# Metaldetector2.net
KiCad netlist of a schematic drawn in EAGLE
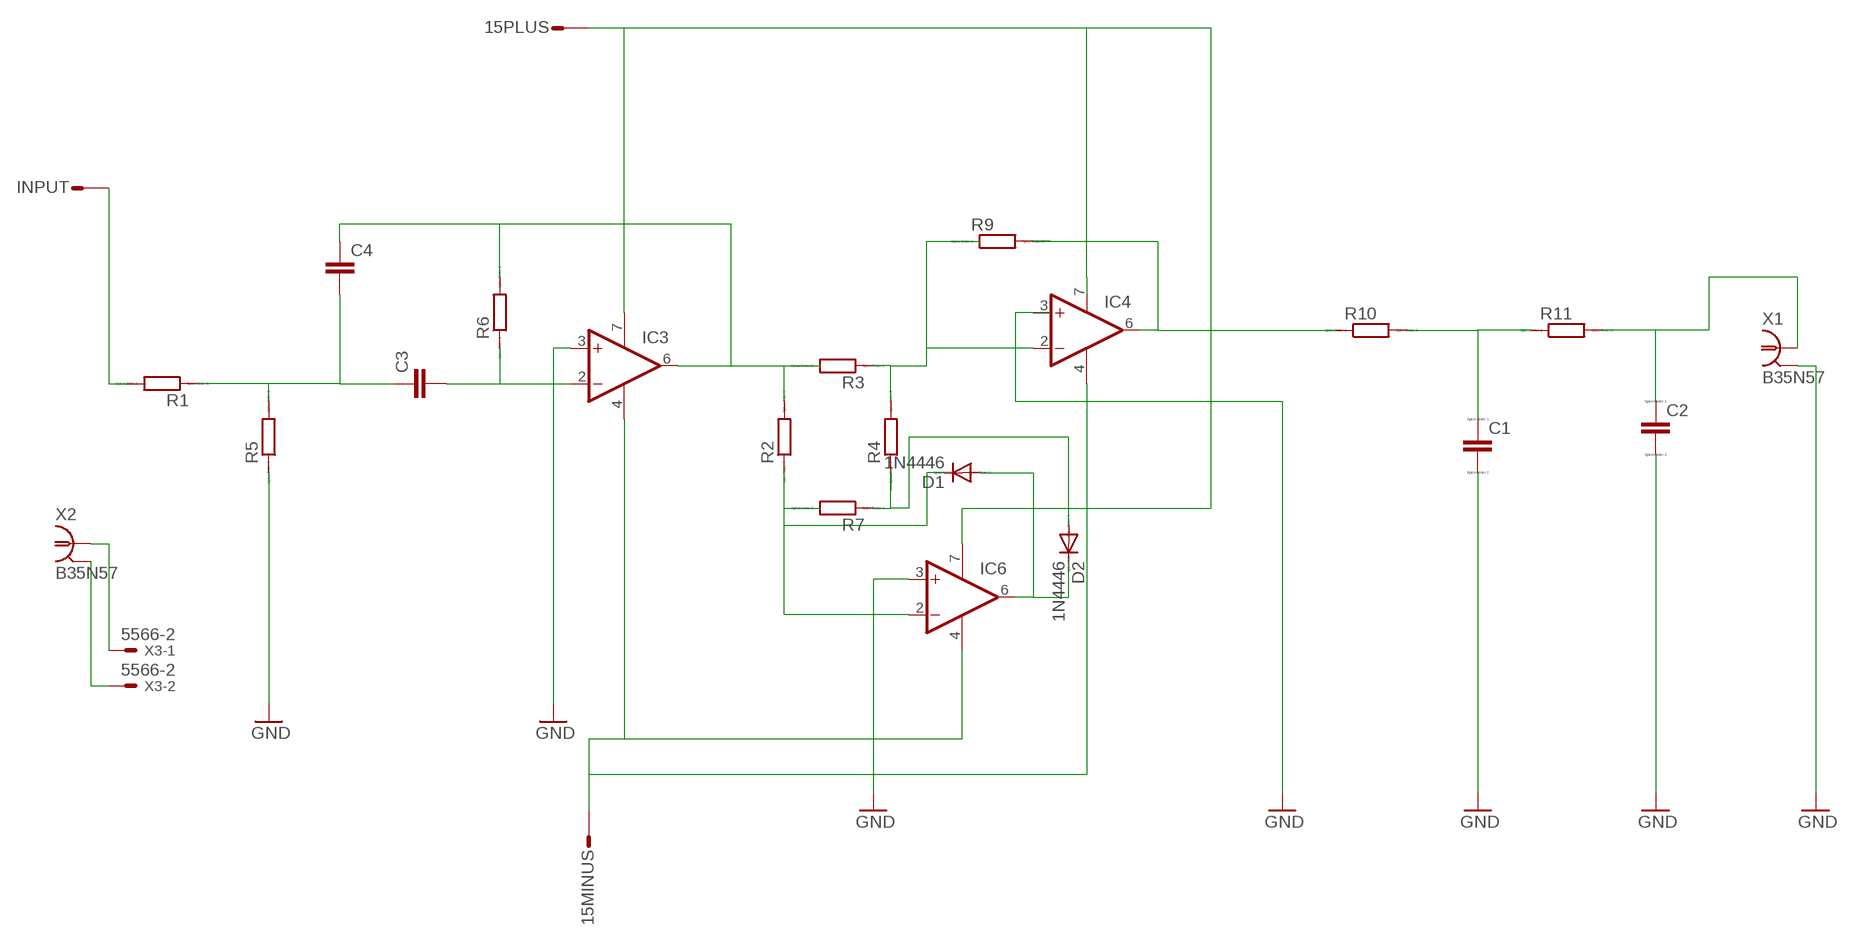
[diagram p0: schematic, sheet 1]

(export (version "E")
  (design (tool "Eeschema 10.0.6"))
  (components
    (comp (ref "15MINUS")
      (value "ST2,8")
      (footprint "eagle-import:ST2,8")
      (libsource (lib "eagle-import") (part "ST2,8"))
    )
    (comp (ref "15PLUS")
      (value "ST2,8")
      (footprint "eagle-import:ST2,8")
      (libsource (lib "eagle-import") (part "ST2,8"))
    )
    (comp (ref "C1")
      (value "C-EU025-040X050")
      (footprint "eagle-import:C025-040X050")
      (libsource (lib "eagle-import") (part "C-EU025-040X050"))
    )
    (comp (ref "C2")
      (value "C-EU025-040X050")
      (footprint "eagle-import:C025-040X050")
      (libsource (lib "eagle-import") (part "C-EU025-040X050"))
    )
    (comp (ref "C3")
      (value "C2.5/5")
      (footprint "eagle-import:C2.5-5")
      (libsource (lib "eagle-import") (part "C2.5/5"))
    )
    (comp (ref "C4")
      (value "C2.5/5")
      (footprint "eagle-import:C2.5-5")
      (libsource (lib "eagle-import") (part "C2.5/5"))
    )
    (comp (ref "D1")
      (value "1N4446")
      (footprint "eagle-import:DO35-10")
      (libsource (lib "eagle-import") (part "1N4446"))
    )
    (comp (ref "D2")
      (value "1N4446")
      (footprint "eagle-import:DO35-10")
      (libsource (lib "eagle-import") (part "1N4446"))
    )
    (comp (ref "IC3")
      (value "1AMP_P7+4N")
      (footprint "eagle-import:DIL08")
      (libsource (lib "eagle-import") (part "1AMP_P7+4N"))
    )
    (comp (ref "IC4")
      (value "1AMP_P7+4N")
      (footprint "eagle-import:DIL08")
      (libsource (lib "eagle-import") (part "1AMP_P7+4N"))
    )
    (comp (ref "IC6")
      (value "1AMP_P7+4N")
      (footprint "eagle-import:DIL08")
      (libsource (lib "eagle-import") (part "1AMP_P7+4N"))
    )
    (comp (ref "INPUT")
      (value "ST2,8")
      (footprint "eagle-import:ST2,8")
      (libsource (lib "eagle-import") (part "ST2,8"))
    )
    (comp (ref "R1")
      (value "R0207/10")
      (footprint "eagle-import:0207_10")
      (libsource (lib "eagle-import") (part "R0207/10"))
    )
    (comp (ref "R2")
      (value "R0207/10")
      (footprint "eagle-import:0207_10")
      (libsource (lib "eagle-import") (part "R0207/10"))
    )
    (comp (ref "R3")
      (value "R0207/10")
      (footprint "eagle-import:0207_10")
      (libsource (lib "eagle-import") (part "R0207/10"))
    )
    (comp (ref "R4")
      (value "R0207/10")
      (footprint "eagle-import:0207_10")
      (libsource (lib "eagle-import") (part "R0207/10"))
    )
    (comp (ref "R5")
      (value "R0207/10")
      (footprint "eagle-import:0207_10")
      (libsource (lib "eagle-import") (part "R0207/10"))
    )
    (comp (ref "R6")
      (value "R0207/10")
      (footprint "eagle-import:0207_10")
      (libsource (lib "eagle-import") (part "R0207/10"))
    )
    (comp (ref "R7")
      (value "R0207/10")
      (footprint "eagle-import:0207_10")
      (libsource (lib "eagle-import") (part "R0207/10"))
    )
    (comp (ref "R9")
      (value "R0207/10")
      (footprint "eagle-import:0207_10")
      (libsource (lib "eagle-import") (part "R0207/10"))
    )
    (comp (ref "R10")
      (value "R0204/7")
      (footprint "eagle-import:0204_7")
      (libsource (lib "eagle-import") (part "R0204/7"))
    )
    (comp (ref "R11")
      (value "R0204/7")
      (footprint "eagle-import:0204_7")
      (libsource (lib "eagle-import") (part "R0204/7"))
    )
    (comp (ref "X1")
      (value "B35N57")
      (footprint "eagle-import:B35N57")
      (libsource (lib "eagle-import") (part "B35N57"))
    )
    (comp (ref "X2")
      (value "B35N57")
      (footprint "eagle-import:B35N57")
      (libsource (lib "eagle-import") (part "B35N57"))
    )
    (comp (ref "X3")
      (value "5566-2")
      (footprint "eagle-import:5566-2")
      (libsource (lib "eagle-import") (part "5566-2"))
    )
  )
  (nets
    (net (code "1") (name "GND") (class "Default")
      (node (ref "C1") (pin "2") (pinfunction "2_2") (pintype "passive"))
      (node (ref "C2") (pin "2") (pinfunction "2_2") (pintype "passive"))
      (node (ref "IC3") (pin "3") (pinfunction "+IN_3") (pintype "input"))
      (node (ref "IC4") (pin "3") (pinfunction "+IN_3") (pintype "input"))
      (node (ref "IC6") (pin "3") (pinfunction "+IN_3") (pintype "input"))
      (node (ref "R5") (pin "1") (pinfunction "1_1") (pintype "passive"))
      (node (ref "X1") (pin "2") (pinfunction "2_2") (pintype "passive"))
      (node (ref "X1") (pin "3") (pinfunction "2_3") (pintype "passive"))
      (node (ref "X1") (pin "4") (pinfunction "2_4") (pintype "passive"))
      (node (ref "X1") (pin "5") (pinfunction "2_5") (pintype "passive"))
    )
    (net (code "2") (name "Net-(15MINUS-ST)") (class "Default")
      (node (ref "15MINUS") (pin "1") (pinfunction "ST_1") (pintype "passive"))
      (node (ref "IC3") (pin "4") (pinfunction "V-_4") (pintype "power_in"))
      (node (ref "IC4") (pin "4") (pinfunction "V-_4") (pintype "power_in"))
      (node (ref "IC6") (pin "4") (pinfunction "V-_4") (pintype "power_in"))
    )
    (net (code "3") (name "Net-(15PLUS-ST)") (class "Default")
      (node (ref "15PLUS") (pin "1") (pinfunction "ST_1") (pintype "passive"))
      (node (ref "IC3") (pin "7") (pinfunction "V+_7") (pintype "power_in"))
      (node (ref "IC4") (pin "7") (pinfunction "V+_7") (pintype "power_in"))
      (node (ref "IC6") (pin "7") (pinfunction "V+_7") (pintype "power_in"))
    )
    (net (code "4") (name "Net-(C1-Pad1)") (class "Default")
      (node (ref "C1") (pin "1") (pinfunction "1_1") (pintype "passive"))
      (node (ref "R10") (pin "2") (pinfunction "2_2") (pintype "passive"))
      (node (ref "R11") (pin "1") (pinfunction "1_1") (pintype "passive"))
    )
    (net (code "5") (name "Net-(C2-Pad1)") (class "Default")
      (node (ref "C2") (pin "1") (pinfunction "1_1") (pintype "passive"))
      (node (ref "R11") (pin "2") (pinfunction "2_2") (pintype "passive"))
      (node (ref "X1") (pin "1") (pinfunction "1_1") (pintype "passive"))
    )
    (net (code "6") (name "Net-(C3-Pad1)") (class "Default")
      (node (ref "C3") (pin "1") (pinfunction "1_1") (pintype "passive"))
      (node (ref "C4") (pin "2") (pinfunction "2_2") (pintype "passive"))
      (node (ref "R1") (pin "1") (pinfunction "1_1") (pintype "passive"))
      (node (ref "R5") (pin "2") (pinfunction "2_2") (pintype "passive"))
    )
    (net (code "7") (name "Net-(D2-PadA)") (class "Default")
      (node (ref "D2") (pin "A") (pinfunction "A_A") (pintype "passive"))
      (node (ref "R4") (pin "1") (pinfunction "1_1") (pintype "passive"))
      (node (ref "R7") (pin "1") (pinfunction "1_1") (pintype "passive"))
    )
    (net (code "8") (name "Net-(IC3--IN)") (class "Default")
      (node (ref "C3") (pin "2") (pinfunction "2_2") (pintype "passive"))
      (node (ref "IC3") (pin "2") (pinfunction "-IN_2") (pintype "input"))
      (node (ref "R6") (pin "1") (pinfunction "1_1") (pintype "passive"))
    )
    (net (code "9") (name "Net-(IC3-OUT)") (class "Default")
      (node (ref "C4") (pin "1") (pinfunction "1_1") (pintype "passive"))
      (node (ref "IC3") (pin "6") (pinfunction "OUT_6") (pintype "output"))
      (node (ref "R2") (pin "2") (pinfunction "2_2") (pintype "passive"))
      (node (ref "R3") (pin "2") (pinfunction "2_2") (pintype "passive"))
      (node (ref "R6") (pin "2") (pinfunction "2_2") (pintype "passive"))
    )
    (net (code "10") (name "Net-(IC4--IN)") (class "Default")
      (node (ref "IC4") (pin "2") (pinfunction "-IN_2") (pintype "input"))
      (node (ref "R3") (pin "1") (pinfunction "1_1") (pintype "passive"))
      (node (ref "R4") (pin "2") (pinfunction "2_2") (pintype "passive"))
      (node (ref "R9") (pin "1") (pinfunction "1_1") (pintype "passive"))
    )
    (net (code "11") (name "Net-(IC4-OUT)") (class "Default")
      (node (ref "IC4") (pin "6") (pinfunction "OUT_6") (pintype "output"))
      (node (ref "R10") (pin "1") (pinfunction "1_1") (pintype "passive"))
      (node (ref "R9") (pin "2") (pinfunction "2_2") (pintype "passive"))
    )
    (net (code "12") (name "Net-(IC6--IN)") (class "Default")
      (node (ref "D1") (pin "C") (pinfunction "C_C") (pintype "passive"))
      (node (ref "IC6") (pin "2") (pinfunction "-IN_2") (pintype "input"))
      (node (ref "R2") (pin "1") (pinfunction "1_1") (pintype "passive"))
      (node (ref "R7") (pin "2") (pinfunction "2_2") (pintype "passive"))
    )
    (net (code "13") (name "Net-(IC6-OUT)") (class "Default")
      (node (ref "D1") (pin "A") (pinfunction "A_A") (pintype "passive"))
      (node (ref "D2") (pin "C") (pinfunction "C_C") (pintype "passive"))
      (node (ref "IC6") (pin "6") (pinfunction "OUT_6") (pintype "output"))
    )
    (net (code "14") (name "Net-(INPUT-ST)") (class "Default")
      (node (ref "INPUT") (pin "1") (pinfunction "ST_1") (pintype "passive"))
      (node (ref "R1") (pin "2") (pinfunction "2_2") (pintype "passive"))
    )
    (net (code "15") (name "Net-(X3A-S)") (class "Default")
      (node (ref "X2") (pin "1") (pinfunction "1_1") (pintype "passive"))
      (node (ref "X3") (pin "1") (pinfunction "S_1") (pintype "passive"))
    )
    (net (code "16") (name "Net-(X3B-S)") (class "Default")
      (node (ref "X2") (pin "2") (pinfunction "2_2") (pintype "passive"))
      (node (ref "X2") (pin "3") (pinfunction "2_3") (pintype "passive"))
      (node (ref "X2") (pin "4") (pinfunction "2_4") (pintype "passive"))
      (node (ref "X2") (pin "5") (pinfunction "2_5") (pintype "passive"))
      (node (ref "X3") (pin "2") (pinfunction "S_2") (pintype "passive"))
    )
  )
)
